# 07_PS_ETH_RJ45.net
KiCad netlist of a schematic drawn in Altium Designer
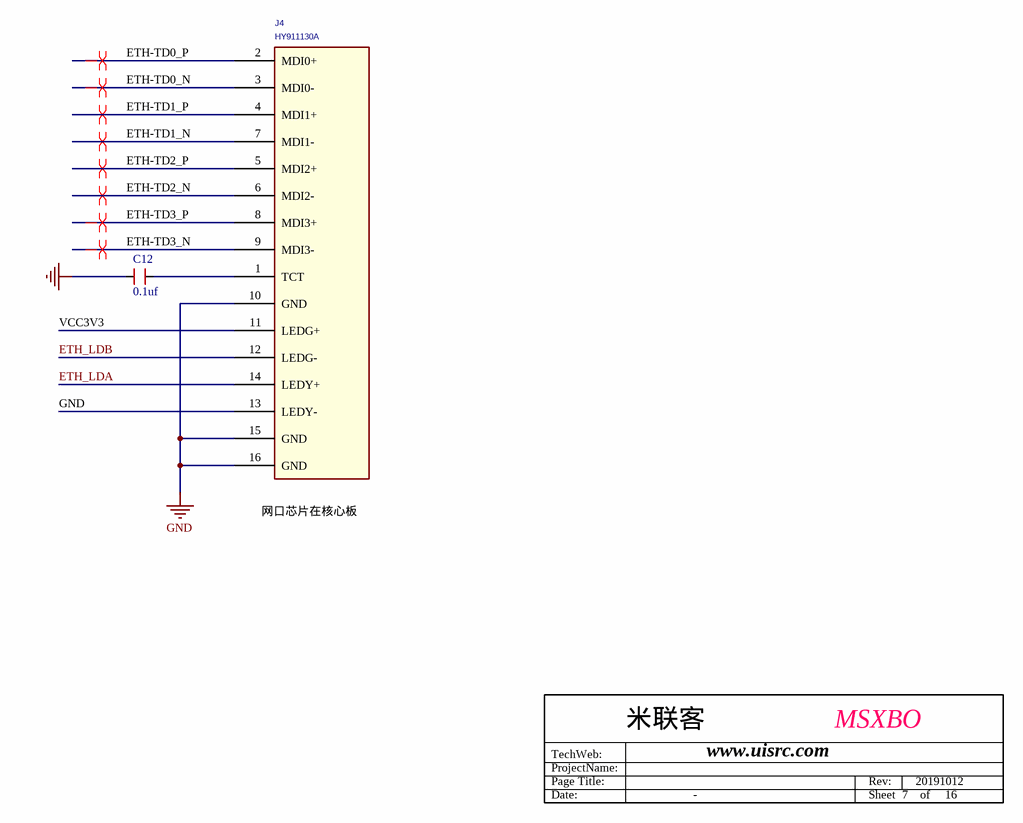
[diagram p0: 07_PS_ETH_RJ45.SchDoc]

(export (version "E")
  (design (tool "Eeschema 10.0.6"))
  (components
    (comp (ref "C12")
      (value "0.1uf")
      (footprint "CAP0603")
      (description "Generic Capacitor")
      (libsource (lib "Miz701_fun20160215") (part "CAPACITOR"))
    )
    (comp (ref "J4") (value "HY911130A") (footprint "HY911130A") (libsource (lib "*") (part "HY911130A")))
  )
  (nets
    (net (code "1") (name "/ETH-TD0_N") (class "Default")
      (node (ref "J4") (pin "3") (pinfunction "MDI0-_3") (pintype "passive"))
    )
    (net (code "2") (name "/ETH-TD0_P") (class "Default")
      (node (ref "J4") (pin "2") (pinfunction "MDI0+_2") (pintype "passive"))
    )
    (net (code "3") (name "/ETH-TD1_N") (class "Default")
      (node (ref "J4") (pin "7") (pinfunction "MDI1-_7") (pintype "passive"))
    )
    (net (code "4") (name "/ETH-TD1_P") (class "Default")
      (node (ref "J4") (pin "4") (pinfunction "MDI1+_4") (pintype "passive"))
    )
    (net (code "5") (name "/ETH-TD2_N") (class "Default")
      (node (ref "J4") (pin "6") (pinfunction "MDI2-_6") (pintype "passive"))
    )
    (net (code "6") (name "/ETH-TD2_P") (class "Default")
      (node (ref "J4") (pin "5") (pinfunction "MDI2+_5") (pintype "passive"))
    )
    (net (code "7") (name "/ETH-TD3_N") (class "Default")
      (node (ref "J4") (pin "9") (pinfunction "MDI3-_9") (pintype "passive"))
    )
    (net (code "8") (name "/ETH-TD3_P") (class "Default")
      (node (ref "J4") (pin "8") (pinfunction "MDI3+_8") (pintype "passive"))
    )
    (net (code "9") (name "/ETH_LDA") (class "Default")
      (node (ref "J4") (pin "14") (pinfunction "LEDY+_14") (pintype "passive"))
    )
    (net (code "10") (name "/ETH_LDB") (class "Default")
      (node (ref "J4") (pin "12") (pinfunction "LEDG-_12") (pintype "passive"))
    )
    (net (code "11") (name "/VCC3V3") (class "Default")
      (node (ref "J4") (pin "11") (pinfunction "LEDG+_11") (pintype "passive"))
    )
    (net (code "12") (name "GND") (class "Default")
      (node (ref "C12") (pin "1") (pinfunction "1_1") (pintype "passive"))
      (node (ref "J4") (pin "10") (pinfunction "GND_10") (pintype "power_in"))
      (node (ref "J4") (pin "13") (pinfunction "LEDY-_13") (pintype "passive"))
      (node (ref "J4") (pin "15") (pinfunction "GND_15") (pintype "power_in"))
      (node (ref "J4") (pin "16") (pinfunction "GND_16") (pintype "power_in"))
    )
    (net (code "13") (name "Net-(J4-TCT)") (class "Default")
      (node (ref "C12") (pin "2") (pinfunction "2_2") (pintype "passive"))
      (node (ref "J4") (pin "1") (pinfunction "TCT_1") (pintype "passive"))
    )
  )
)
